# PCB-TCH-MENU2.net
KiCad netlist of a schematic drawn in EAGLE
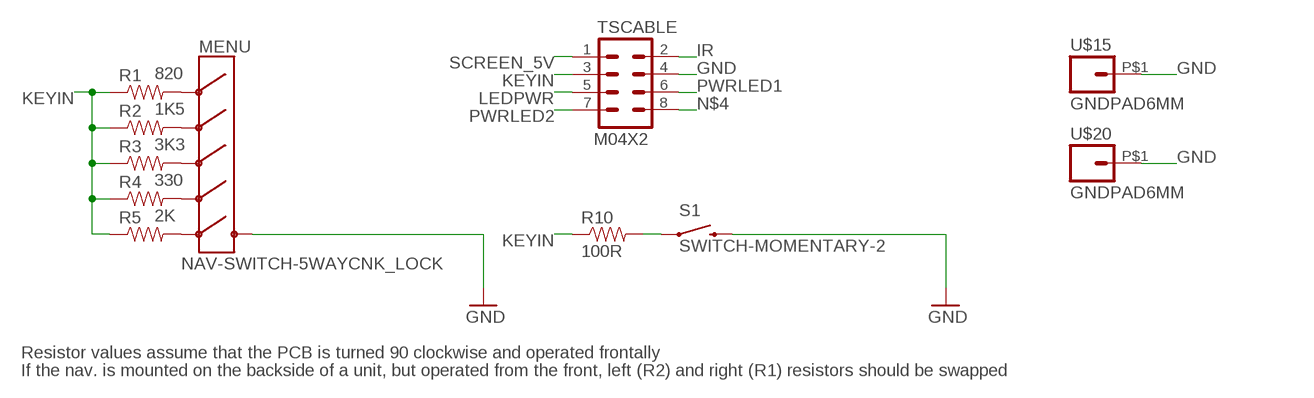
[diagram p0: schematic, sheet 1]

(export (version "E")
  (design (tool "Eeschema 10.0.6"))
  (components
    (comp (ref "MENU")
      (value "NAV-SWITCH-5WAYCNK_LOCK")
      (footprint "eagle-import:NAV-SWITCH-5WAY")
      (libsource (lib "eagle-import") (part "NAV-SWITCH-5WAYCNK_LOCK"))
    )
    (comp (ref "R1")
      (value "820")
      (footprint "eagle-import:0603-RES")
      (libsource (lib "eagle-import") (part "RESISTOR0603-RES"))
    )
    (comp (ref "R2")
      (value "1K5")
      (footprint "eagle-import:0603-RES")
      (libsource (lib "eagle-import") (part "RESISTOR0603-RES"))
    )
    (comp (ref "R3")
      (value "3K3")
      (footprint "eagle-import:0603-RES")
      (libsource (lib "eagle-import") (part "RESISTOR0603-RES"))
    )
    (comp (ref "R4")
      (value "330")
      (footprint "eagle-import:0603-RES")
      (libsource (lib "eagle-import") (part "RESISTOR0603-RES"))
    )
    (comp (ref "R5")
      (value "2K")
      (footprint "eagle-import:0603-RES")
      (libsource (lib "eagle-import") (part "RESISTOR0603-RES"))
    )
    (comp (ref "R10")
      (value "100R")
      (footprint "eagle-import:0603-RES")
      (libsource (lib "eagle-import") (part "RESISTOR0603-RES"))
    )
    (comp (ref "S1")
      (value "SWITCH-MOMENTARY-2")
      (footprint "eagle-import:TACTILE_SWITCH_TALL")
      (libsource (lib "eagle-import") (part "SWITCH-MOMENTARY-2"))
    )
    (comp (ref "TSCABLE")
      (value "M04X2")
      (footprint "eagle-import:2X4")
      (libsource (lib "eagle-import") (part "M04X2"))
    )
    (comp (ref "U$15")
      (value "GNDPAD6MM")
      (footprint "eagle-import:3.2MMPAD6MM")
      (libsource (lib "eagle-import") (part "GNDPAD6MM"))
    )
    (comp (ref "U$20")
      (value "GNDPAD6MM")
      (footprint "eagle-import:3.2MMPAD6MM")
      (libsource (lib "eagle-import") (part "GNDPAD6MM"))
    )
  )
  (nets
    (net (code "1") (name "/IR") (class "Default")
      (node (ref "TSCABLE") (pin "2") (pinfunction "2_2") (pintype "passive"))
    )
    (net (code "2") (name "/KEYIN") (class "Default")
      (node (ref "R1") (pin "1") (pinfunction "1_1") (pintype "passive"))
      (node (ref "R10") (pin "1") (pinfunction "1_1") (pintype "passive"))
      (node (ref "R2") (pin "1") (pinfunction "1_1") (pintype "passive"))
      (node (ref "R3") (pin "1") (pinfunction "1_1") (pintype "passive"))
      (node (ref "R4") (pin "1") (pinfunction "1_1") (pintype "passive"))
      (node (ref "R5") (pin "1") (pinfunction "1_1") (pintype "passive"))
      (node (ref "TSCABLE") (pin "3") (pinfunction "3_3") (pintype "passive"))
    )
    (net (code "3") (name "/LEDPWR") (class "Default")
      (node (ref "TSCABLE") (pin "5") (pinfunction "5_5") (pintype "passive"))
    )
    (net (code "4") (name "/N$4") (class "Default")
      (node (ref "TSCABLE") (pin "8") (pinfunction "8_8") (pintype "passive"))
    )
    (net (code "5") (name "/PWRLED1") (class "Default")
      (node (ref "TSCABLE") (pin "6") (pinfunction "6_6") (pintype "passive"))
    )
    (net (code "6") (name "/PWRLED2") (class "Default")
      (node (ref "TSCABLE") (pin "7") (pinfunction "7_7") (pintype "passive"))
    )
    (net (code "7") (name "/SCREEN_5V") (class "Default")
      (node (ref "TSCABLE") (pin "1") (pinfunction "1_1") (pintype "passive"))
    )
    (net (code "8") (name "GND") (class "Default")
      (node (ref "MENU") (pin "PIN4") (pinfunction "COMMON_PIN4") (pintype "bidirectional"))
      (node (ref "S1") (pin "B2") (pinfunction "2_B2") (pintype "passive"))
      (node (ref "TSCABLE") (pin "4") (pinfunction "4_4") (pintype "passive"))
      (node (ref "U$15") (pin "P$1") (pinfunction "1_P$1") (pintype "passive"))
      (node (ref "U$20") (pin "P$1") (pinfunction "1_P$1") (pintype "passive"))
    )
    (net (code "9") (name "Net-(MENU-DWN)") (class "Default")
      (node (ref "MENU") (pin "PIN3") (pinfunction "DWN_PIN3") (pintype "bidirectional"))
      (node (ref "R2") (pin "2") (pinfunction "2_2") (pintype "passive"))
    )
    (net (code "10") (name "Net-(MENU-LEFT)") (class "Default")
      (node (ref "MENU") (pin "PIN2") (pinfunction "LEFT_PIN2") (pintype "bidirectional"))
      (node (ref "R3") (pin "2") (pinfunction "2_2") (pintype "passive"))
    )
    (net (code "11") (name "Net-(MENU-PUSH)") (class "Default")
      (node (ref "MENU") (pin "PIN6") (pinfunction "PUSH_PIN6") (pintype "bidirectional"))
      (node (ref "R5") (pin "2") (pinfunction "2_2") (pintype "passive"))
    )
    (net (code "12") (name "Net-(MENU-RIGHT)") (class "Default")
      (node (ref "MENU") (pin "PIN5") (pinfunction "RIGHT_PIN5") (pintype "bidirectional"))
      (node (ref "R4") (pin "2") (pinfunction "2_2") (pintype "passive"))
    )
    (net (code "13") (name "Net-(MENU-UP)") (class "Default")
      (node (ref "MENU") (pin "PIN1") (pinfunction "UP_PIN1") (pintype "bidirectional"))
      (node (ref "R1") (pin "2") (pinfunction "2_2") (pintype "passive"))
    )
    (net (code "14") (name "Net-(S1-1)") (class "Default")
      (node (ref "R10") (pin "2") (pinfunction "2_2") (pintype "passive"))
      (node (ref "S1") (pin "A2") (pinfunction "1_A2") (pintype "passive"))
    )
  )
)
